# MCPICKUP.net
KiCad netlist of a schematic drawn in EasyEDA
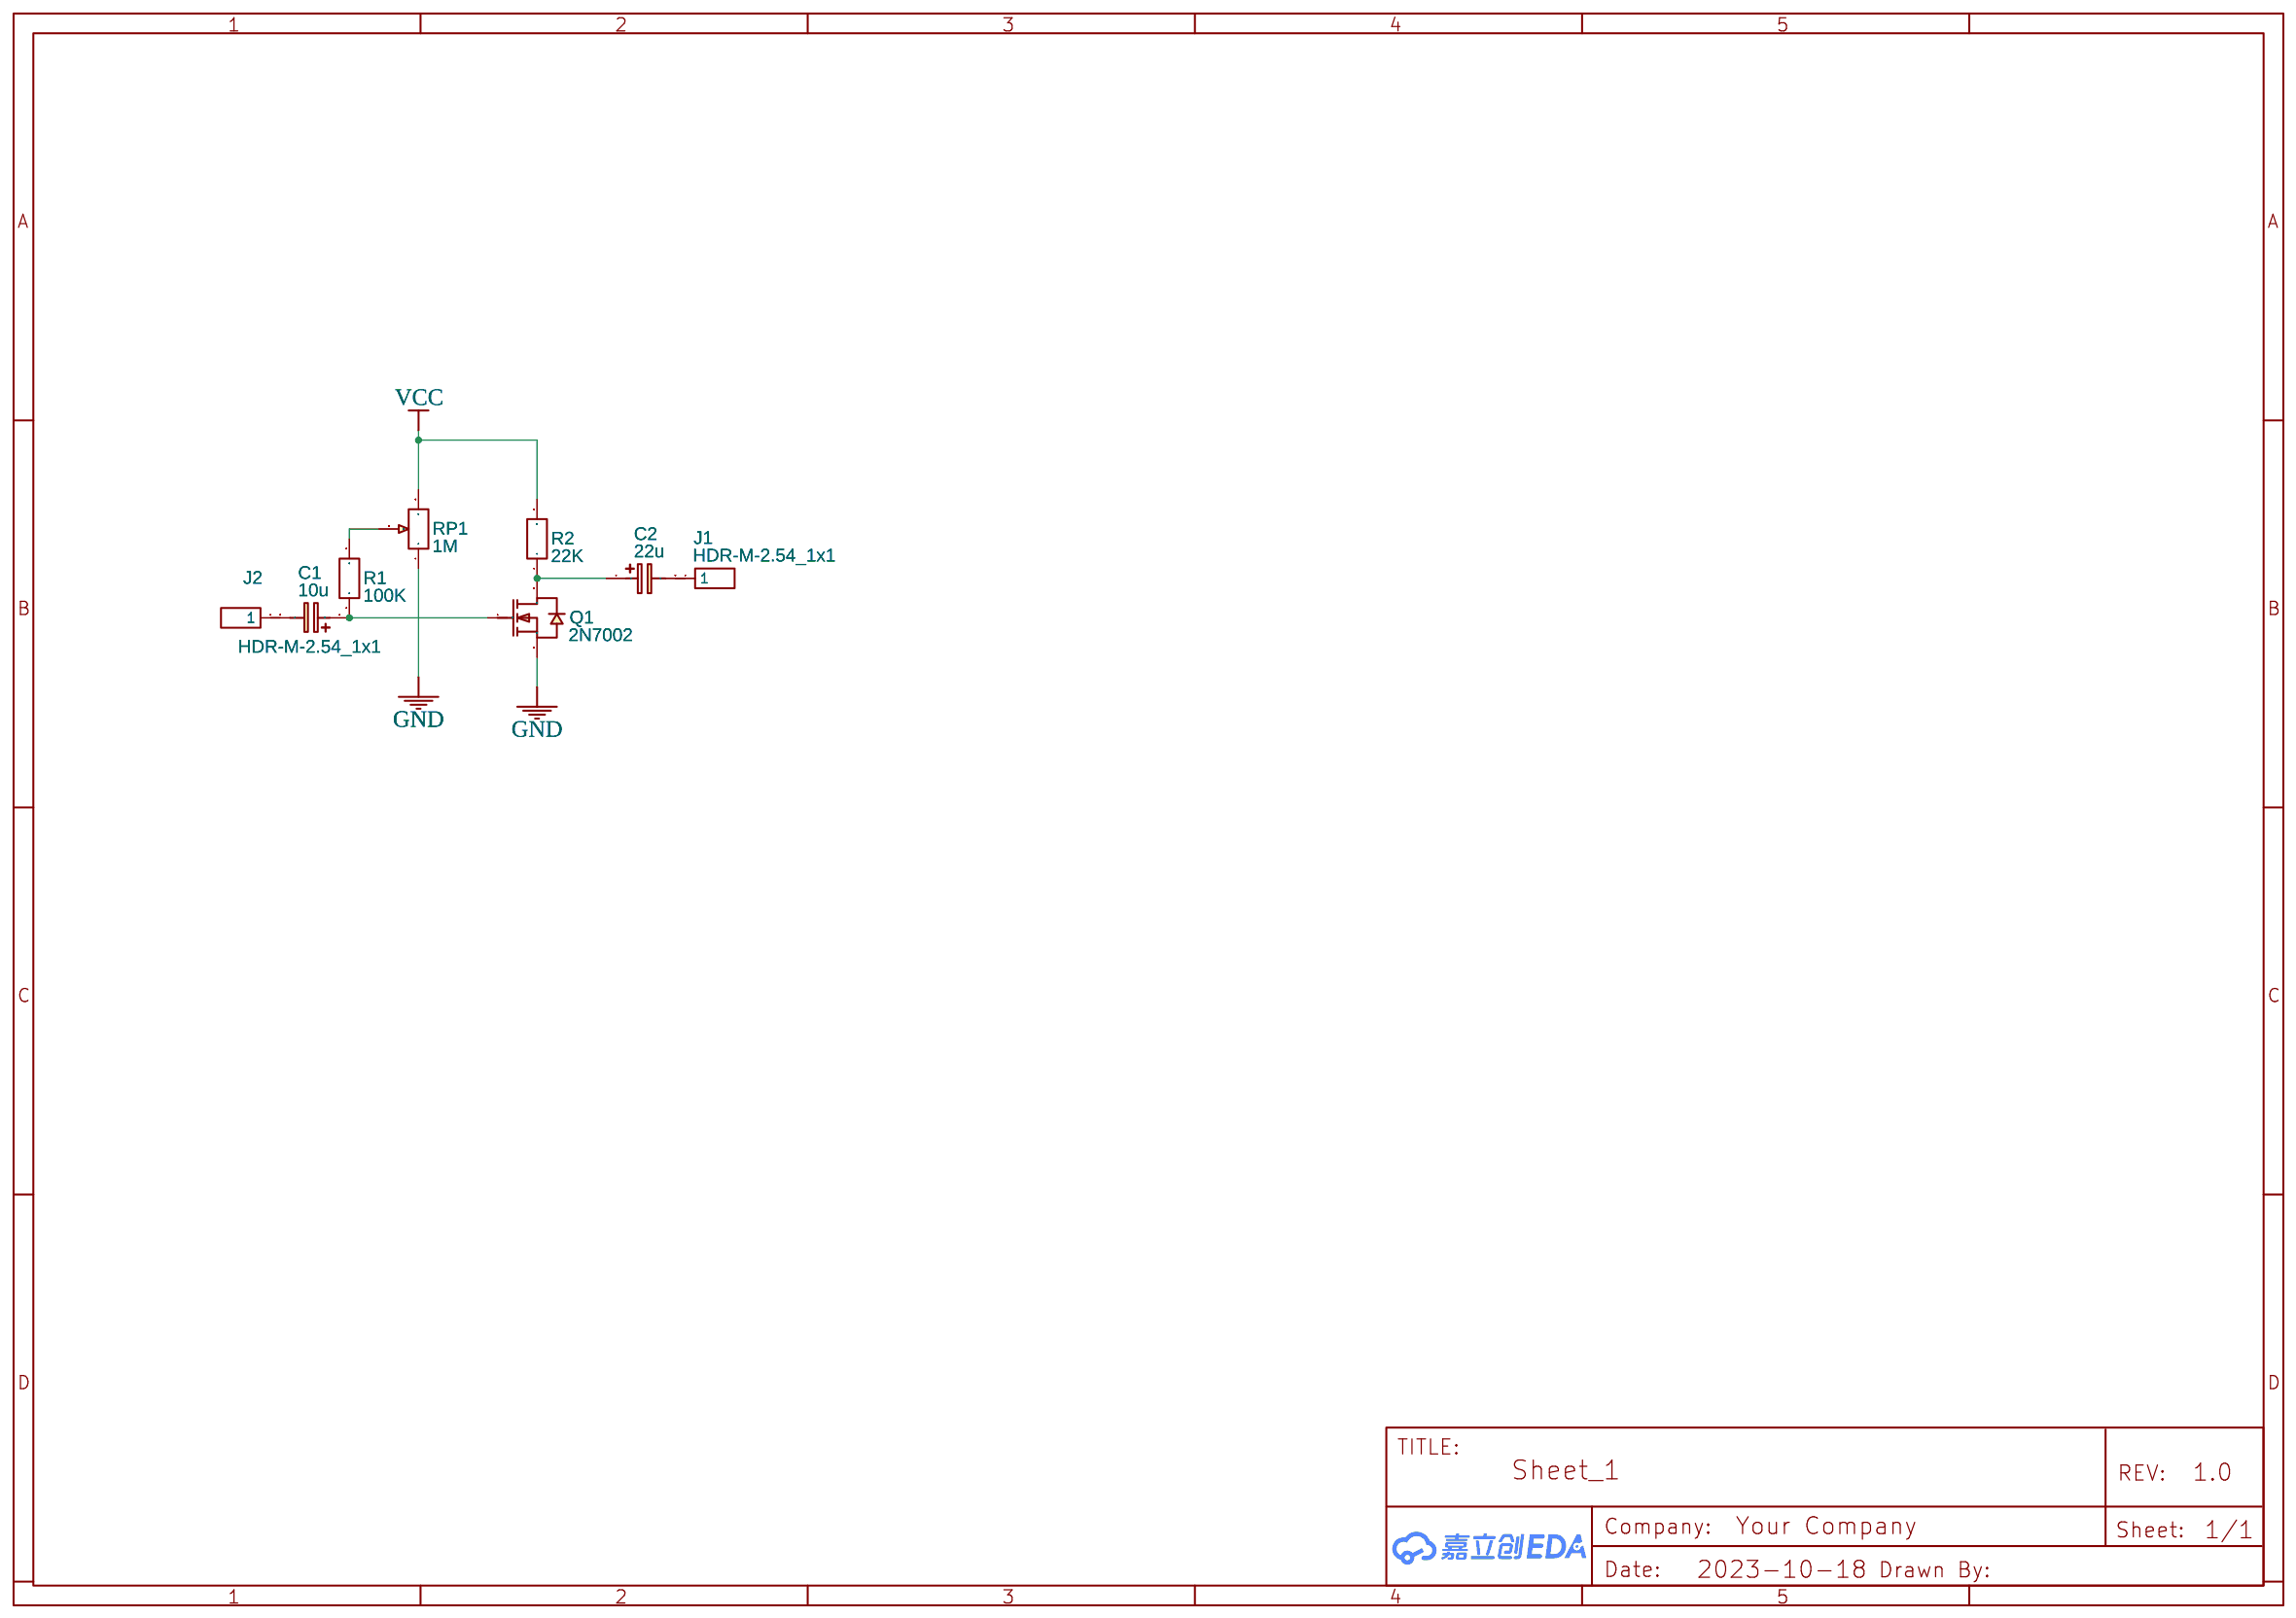
[diagram p0: schematic sheet]

(export (version "E")
  (design (tool "Eeschema 10.0.6"))
  (components
    (comp (ref "C1") (value "10u") (libsource (lib "") (part "C_Tan_SMD_A_EU_1")))
    (comp (ref "C2") (value "22u") (libsource (lib "") (part "C_Tan_SMD_A_EU")))
    (comp (ref "J1")
      (value "HDR-M-2.54_1x1")
      (fields (field (name "BOM_Supplier Part") "C81276"))
      (libsource (lib "") (part "HDR-M-2.54_1x1"))
    )
    (comp (ref "J2")
      (value "HDR-M-2.54_1x1")
      (fields (field (name "BOM_Supplier Part") "C81276"))
      (libsource (lib "") (part "HDR-M-2.54_1x1_1"))
    )
    (comp (ref "Q1")
      (value "2N7002")
      (fields (field (name "BOM_Manufacturer Part") "2N7002,215") (field (name "BOM_Supplier Part") "C65189"))
      (libsource (lib "") (part "2N7002"))
    )
    (comp (ref "R1") (value "100K") (libsource (lib "") (part "R_0603_EU")))
    (comp (ref "R2") (value "22K") (libsource (lib "") (part "R_0603_EU")))
    (comp (ref "RP1") (value "1M") (libsource (lib "") (part "R_3296W_EU")))
  )
  (nets
    (net (code "1") (name "GND") (class "Default")
      (node (ref "Q1") (pin "2") (pinfunction "S_2") (pintype "unspecified"))
      (node (ref "RP1") (pin "1") (pinfunction "1_1") (pintype "input"))
    )
    (net (code "2") (name "Net-(Q1-D)") (class "Default")
      (node (ref "C2") (pin "1") (pinfunction "1_1") (pintype "unspecified"))
      (node (ref "Q1") (pin "3") (pinfunction "D_3") (pintype "unspecified"))
      (node (ref "R2") (pin "1") (pinfunction "1_1") (pintype "unspecified"))
    )
    (net (code "3") (name "Net-(Q1-G)") (class "Default")
      (node (ref "C1") (pin "1") (pinfunction "1_1") (pintype "unspecified"))
      (node (ref "Q1") (pin "1") (pinfunction "G_1") (pintype "unspecified"))
      (node (ref "R1") (pin "1") (pinfunction "1_1") (pintype "unspecified"))
    )
    (net (code "4") (name "Net-(R1-Pad2)") (class "Default")
      (node (ref "R1") (pin "2") (pinfunction "2_2") (pintype "unspecified"))
      (node (ref "RP1") (pin "2") (pinfunction "2_2") (pintype "input"))
    )
    (net (code "5") (name "VCC") (class "Default")
      (node (ref "R2") (pin "2") (pinfunction "2_2") (pintype "unspecified"))
      (node (ref "RP1") (pin "3") (pinfunction "3_3") (pintype "input"))
    )
    (net (code "6") (name "unconnected-(C1-Pad2)") (class "Default")
      (node (ref "C1") (pin "2") (pinfunction "2_2") (pintype "unspecified"))
    )
    (net (code "7") (name "unconnected-(C2-Pad2)") (class "Default")
      (node (ref "C2") (pin "2") (pinfunction "2_2") (pintype "unspecified"))
    )
    (net (code "8") (name "unconnected-(J1-Pad1)") (class "Default")
      (node (ref "J1") (pin "1") (pinfunction "1_1") (pintype "input"))
    )
    (net (code "9") (name "unconnected-(J2-Pad1)") (class "Default")
      (node (ref "J2") (pin "1") (pinfunction "1_1") (pintype "input"))
    )
  )
)
